# H-BRIDGE-SCH.net
KiCad netlist of a schematic drawn in Altium Designer
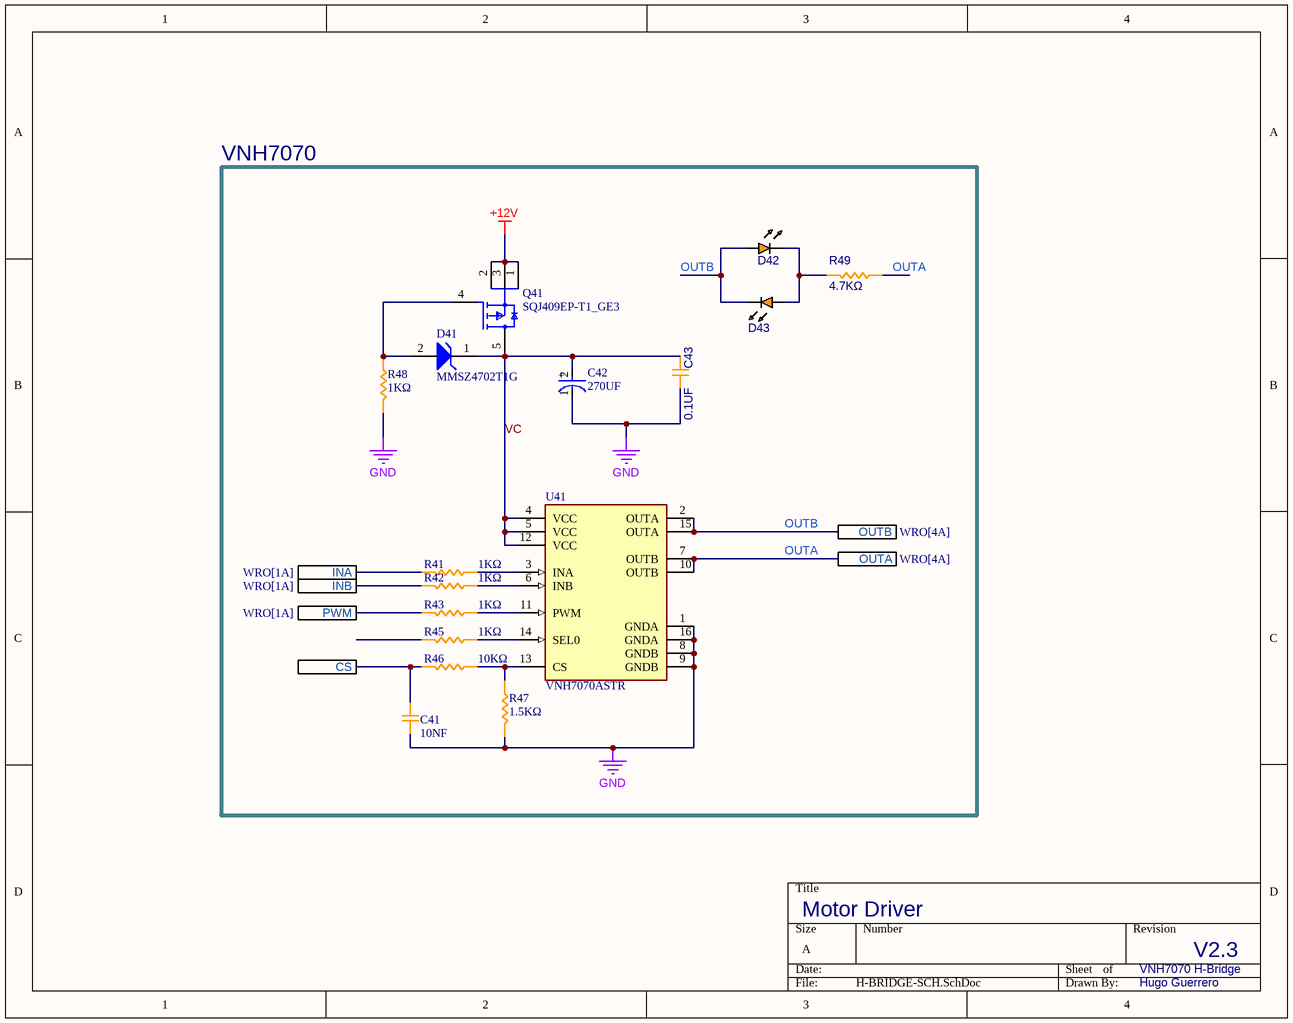
[diagram p0: H-BRIDGE-SCH.SchDoc]

(export (version "E")
  (design (tool "Eeschema 10.0.6"))
  (components
    (comp (ref "C41")
      (value "10NF")
      (footprint "CAP_0603")
      (description "Capacitor SMD 0603 generic")
      (libsource (lib "RC") (part "CAP_0603"))
    )
    (comp (ref "C42")
      (value "270UF")
      (footprint "FP-FTD8-MFG")
      (description "CAP ALUM 220UF 20% 25V SMD")
      (fields (field (name "TOLERANCE") "20%") (field (name "VOLTAGE") "25V"))
      (libsource (lib "Altium Content Vault") (part "cf48714ba7e38822c1575c7ec0b6d1f"))
    )
    (comp (ref "C43")
      (value "0.1UF")
      (footprint "CAP_0603")
      (description "Capacitor SMD 0603 generic")
      (libsource (lib "GenericRC") (part "CAP_0603"))
    )
    (comp (ref "D41")
      (value "MMSZ4702T1G")
      (footprint "ONSC-SOD-123-2-425-04_V")
      (description "Zener Voltage Regulator, 500 mW, 2-Pin SOD-123, Pb-Free, Tape and Reel")
      (fields (field (name "MANUFACTURER") "On Semiconductor"))
      (libsource (lib "Altium Content Vault") (part "ONSC-K1A2-2"))
    )
    (comp (ref "D42")
      (value "LED_0603")
      (footprint "LED_0603")
      (libsource (lib "GenericRC") (part "LED_0603"))
    )
    (comp (ref "D43")
      (value "LED_0603")
      (footprint "LED_0603")
      (libsource (lib "GenericRC") (part "LED_0603"))
    )
    (comp (ref "Q41")
      (value "SQJ409EP-T1_GE3")
      (footprint "FP-T16-0221-SINGLE-MFG")
      (description "MOSFET P-CH 40V 60A POWERPAKSO-8")
      (fields
        (field (name "OCTOPART") "https://octopart.com/sqj409ep-t1_ge3-vishay-82218774")
        (field (name "MANUFACTURER") "Vishay")
      )
      (libsource (lib "Altium Content Vault") (part "4c8c3adca31dd80ec017b82eab9845e"))
    )
    (comp (ref "R41")
      (value "1KΩ")
      (footprint "RES_0603")
      (description "Resistor SMD 0603 generic")
      (libsource (lib "RC") (part "RES_0603"))
    )
    (comp (ref "R42")
      (value "1KΩ")
      (footprint "RES_0603")
      (description "Resistor SMD 0603 generic")
      (libsource (lib "RC") (part "RES_0603"))
    )
    (comp (ref "R43")
      (value "1KΩ")
      (footprint "RES_0603")
      (description "Resistor SMD 0603 generic")
      (libsource (lib "RC") (part "RES_0603"))
    )
    (comp (ref "R45")
      (value "1KΩ")
      (footprint "RES_0603")
      (description "Resistor SMD 0603 generic")
      (libsource (lib "RC") (part "RES_0603"))
    )
    (comp (ref "R46")
      (value "10KΩ")
      (footprint "RES_0603")
      (description "Resistor SMD 0603 generic")
      (libsource (lib "RC") (part "RES_0603"))
    )
    (comp (ref "R47")
      (value "1.5KΩ")
      (footprint "RES_0603")
      (description "Resistor SMD 0603 generic")
      (libsource (lib "RC") (part "RES_0603"))
    )
    (comp (ref "R48")
      (value "1KΩ")
      (footprint "RES_0603")
      (description "Resistor SMD 0603 generic")
      (libsource (lib "RC") (part "RES_0603"))
    )
    (comp (ref "R49")
      (value "4.7KΩ")
      (footprint "RES_0603")
      (description "Resistor SMD 0603 generic")
      (libsource (lib "GenericRC") (part "RES_0603"))
    )
    (comp (ref "U41")
      (value "VNH7070ASTR")
      (footprint "FP-SO-16N-GAPGCFT00818-MFG")
      (description "IC MOTOR DRIVER 4V-28V 16SOIC")
      (fields
        (field (name "MANUFACTURER") "STMicroelectronics")
        (field (name "OCTOPART") "https://octopart.com/vnh7070astr-stmicroelectronics-66668687")
      )
      (libsource (lib "Altium Content Vault") (part "0b40bfafcd93a4d0754fd1674b92a59"))
    )
  )
  (nets
    (net (code "1") (name "+12V") (class "Default")
      (node (ref "Q41") (pin "1") (pinfunction "S_1") (pintype "passive"))
      (node (ref "Q41") (pin "2") (pinfunction "S_2") (pintype "passive"))
      (node (ref "Q41") (pin "3") (pinfunction "S_3") (pintype "passive"))
    )
    (net (code "2") (name "/CS") (class "Default")
      (node (ref "C41") (pin "2") (pintype "passive"))
      (node (ref "R46") (pin "1") (pintype "passive"))
    )
    (net (code "3") (name "/INA") (class "Default") (node (ref "R41") (pin "1") (pintype "passive")))
    (net (code "4") (name "/INB") (class "Default") (node (ref "R42") (pin "1") (pintype "passive")))
    (net (code "5") (name "/OUTA") (class "Default")
      (node (ref "R49") (pin "2") (pintype "passive"))
      (node (ref "U41") (pin "10") (pinfunction "OUTB_10") (pintype "passive"))
      (node (ref "U41") (pin "7") (pinfunction "OUTB_7") (pintype "passive"))
    )
    (net (code "6") (name "/OUTB") (class "Default")
      (node (ref "D42") (pin "A") (pinfunction "2_A") (pintype "passive"))
      (node (ref "D43") (pin "C") (pinfunction "1_C") (pintype "passive"))
      (node (ref "U41") (pin "15") (pinfunction "OUTA_15") (pintype "passive"))
      (node (ref "U41") (pin "2") (pinfunction "OUTA_2") (pintype "passive"))
    )
    (net (code "7") (name "/PWM") (class "Default") (node (ref "R43") (pin "1") (pintype "passive")))
    (net (code "8") (name "/VC") (class "Default")
      (node (ref "C42") (pin "2") (pinfunction "A_2") (pintype "passive"))
      (node (ref "C43") (pin "1") (pintype "passive"))
      (node (ref "D41") (pin "1") (pinfunction "K_1") (pintype "passive"))
      (node (ref "Q41") (pin "5") (pinfunction "D_5") (pintype "passive"))
      (node (ref "U41") (pin "12") (pinfunction "VCC_12") (pintype "power_in"))
      (node (ref "U41") (pin "4") (pinfunction "VCC_4") (pintype "power_in"))
      (node (ref "U41") (pin "5") (pinfunction "VCC_5") (pintype "power_in"))
    )
    (net (code "9") (name "GND") (class "Default")
      (node (ref "C41") (pin "1") (pintype "passive"))
      (node (ref "C42") (pin "1") (pinfunction "C_1") (pintype "passive"))
      (node (ref "C43") (pin "2") (pintype "passive"))
      (node (ref "R47") (pin "1") (pintype "passive"))
      (node (ref "R48") (pin "1") (pintype "passive"))
      (node (ref "U41") (pin "1") (pinfunction "GNDA_1") (pintype "power_in"))
      (node (ref "U41") (pin "16") (pinfunction "GNDA_16") (pintype "power_in"))
      (node (ref "U41") (pin "8") (pinfunction "GNDB_8") (pintype "power_in"))
      (node (ref "U41") (pin "9") (pinfunction "GNDB_9") (pintype "power_in"))
    )
    (net (code "10") (name "Net-(D41-A)") (class "Default")
      (node (ref "D41") (pin "2") (pinfunction "A_2") (pintype "passive"))
      (node (ref "Q41") (pin "4") (pinfunction "G_4") (pintype "passive"))
      (node (ref "R48") (pin "2") (pintype "passive"))
    )
    (net (code "11") (name "Net-(D42-1)") (class "Default")
      (node (ref "D42") (pin "C") (pinfunction "1_C") (pintype "passive"))
      (node (ref "D43") (pin "A") (pinfunction "2_A") (pintype "passive"))
      (node (ref "R49") (pin "1") (pintype "passive"))
    )
    (net (code "12") (name "Net-(U41-CS)") (class "Default")
      (node (ref "R46") (pin "2") (pintype "passive"))
      (node (ref "R47") (pin "2") (pintype "passive"))
      (node (ref "U41") (pin "13") (pinfunction "CS_13") (pintype "passive"))
    )
    (net (code "13") (name "Net-(U41-INA)") (class "Default")
      (node (ref "R41") (pin "2") (pintype "passive"))
      (node (ref "U41") (pin "3") (pinfunction "INA_3") (pintype "input"))
    )
    (net (code "14") (name "Net-(U41-INB)") (class "Default")
      (node (ref "R42") (pin "2") (pintype "passive"))
      (node (ref "U41") (pin "6") (pinfunction "INB_6") (pintype "input"))
    )
    (net (code "15") (name "Net-(U41-PWM)") (class "Default")
      (node (ref "R43") (pin "2") (pintype "passive"))
      (node (ref "U41") (pin "11") (pinfunction "PWM_11") (pintype "input"))
    )
    (net (code "16") (name "Net-(U41-SEL0)") (class "Default")
      (node (ref "R45") (pin "2") (pintype "passive"))
      (node (ref "U41") (pin "14") (pinfunction "SEL0_14") (pintype "input"))
    )
    (net (code "17") (name "unconnected-(R45-Pad1)") (class "Default")
      (node (ref "R45") (pin "1") (pintype "passive"))
    )
  )
)
